# SD.net
KiCad netlist of a schematic drawn in Altium Designer
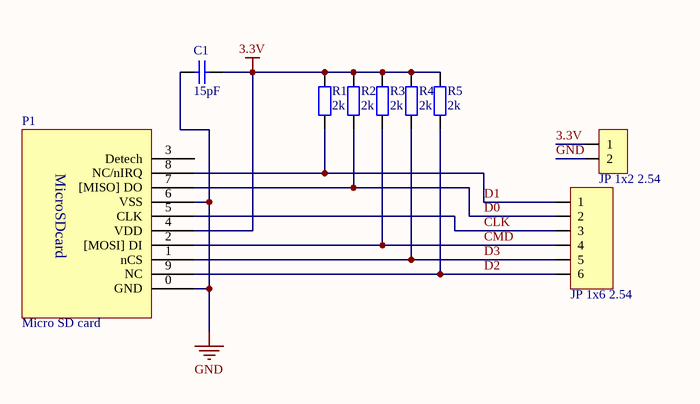
[diagram p0: SD.SchDoc]

(export (version "E")
  (design (tool "Eeschema 10.0.6"))
  (components
    (comp (ref "C1")
      (value "15pF")
      (footprint "tu 0805")
      (description "Dán")
      (libsource (lib "Capacitor") (part "Tu 0805 15pF 50V 10%"))
    )
    (comp (ref "JP1")
      (value "JP 1x6 2.54")
      (footprint "JP 1x6 DT")
      (description "Cắm")
      (libsource (lib "Jump") (part "JP 1x6 2.54 Duc Thang"))
    )
    (comp (ref "JP3")
      (value "JP 1x2 2.54")
      (footprint "JP 1x2 DT")
      (description "Cắm")
      (libsource (lib "Jump") (part "JP 1x2 2.54 Duc Thang"))
    )
    (comp (ref "P1")
      (value "Micro SD card")
      (footprint "MicroSD")
      (libsource (lib "Component") (part "Micro SD card"))
    )
    (comp (ref "R1")
      (value "2k")
      (footprint "tro smd 0805")
      (description "Dán")
      (libsource (lib "Resistor") (part "Tro 0805 1% 2k"))
    )
    (comp (ref "R2")
      (value "2k")
      (footprint "tro smd 0805")
      (description "Dán")
      (libsource (lib "Resistor") (part "Tro 0805 1% 2k"))
    )
    (comp (ref "R3")
      (value "2k")
      (footprint "tro smd 0805")
      (description "Dán")
      (libsource (lib "Resistor") (part "Tro 0805 1% 2k"))
    )
    (comp (ref "R4")
      (value "2k")
      (footprint "tro smd 0805")
      (description "Dán")
      (libsource (lib "Resistor") (part "Tro 0805 1% 2k"))
    )
    (comp (ref "R5")
      (value "2k")
      (footprint "tro smd 0805")
      (description "Dán")
      (libsource (lib "Resistor") (part "Tro 0805 1% 2k"))
    )
  )
  (nets
    (net (code "1") (name "/CLK") (class "Default")
      (node (ref "JP1") (pin "3") (pinfunction "3_3") (pintype "passive"))
      (node (ref "P1") (pin "5") (pinfunction "CLK_5") (pintype "passive"))
    )
    (net (code "2") (name "/CMD") (class "Default")
      (node (ref "JP1") (pin "4") (pinfunction "4_4") (pintype "passive"))
      (node (ref "P1") (pin "2") (pinfunction "[MOSI]_DI_2") (pintype "passive"))
      (node (ref "R3") (pin "1") (pinfunction "1_1") (pintype "passive"))
    )
    (net (code "3") (name "/D0") (class "Default")
      (node (ref "JP1") (pin "2") (pinfunction "2_2") (pintype "passive"))
      (node (ref "P1") (pin "7") (pinfunction "[MISO]_DO_7") (pintype "passive"))
      (node (ref "R2") (pin "1") (pinfunction "1_1") (pintype "passive"))
    )
    (net (code "4") (name "/D1") (class "Default")
      (node (ref "JP1") (pin "1") (pinfunction "1_1") (pintype "passive"))
      (node (ref "P1") (pin "8") (pinfunction "NC/nIRQ_8") (pintype "passive"))
      (node (ref "R1") (pin "1") (pinfunction "1_1") (pintype "passive"))
    )
    (net (code "5") (name "/D2") (class "Default")
      (node (ref "JP1") (pin "6") (pinfunction "6_6") (pintype "passive"))
      (node (ref "P1") (pin "9") (pinfunction "NC_9") (pintype "passive"))
      (node (ref "R5") (pin "1") (pinfunction "1_1") (pintype "passive"))
    )
    (net (code "6") (name "/D3") (class "Default")
      (node (ref "JP1") (pin "5") (pinfunction "5_5") (pintype "passive"))
      (node (ref "P1") (pin "1") (pinfunction "nCS_1") (pintype "passive"))
      (node (ref "R4") (pin "1") (pinfunction "1_1") (pintype "passive"))
    )
    (net (code "7") (name "3.3V") (class "Default")
      (node (ref "C1") (pin "1") (pinfunction "1_1") (pintype "passive"))
      (node (ref "JP3") (pin "1") (pinfunction "1_1") (pintype "passive"))
      (node (ref "P1") (pin "4") (pinfunction "VDD_4") (pintype "passive"))
      (node (ref "R1") (pin "2") (pinfunction "2_2") (pintype "passive"))
      (node (ref "R2") (pin "2") (pinfunction "2_2") (pintype "passive"))
      (node (ref "R3") (pin "2") (pinfunction "2_2") (pintype "passive"))
      (node (ref "R4") (pin "2") (pinfunction "2_2") (pintype "passive"))
      (node (ref "R5") (pin "2") (pinfunction "2_2") (pintype "passive"))
    )
    (net (code "8") (name "GND") (class "Default")
      (node (ref "C1") (pin "2") (pinfunction "2_2") (pintype "passive"))
      (node (ref "JP3") (pin "2") (pinfunction "2_2") (pintype "passive"))
      (node (ref "P1") (pin "0") (pinfunction "GND_0") (pintype "passive"))
      (node (ref "P1") (pin "6") (pinfunction "VSS_6") (pintype "passive"))
    )
    (net (code "9") (name "unconnected-(P1-Detech-Pad3)") (class "Default")
      (node (ref "P1") (pin "3") (pinfunction "Detech_3") (pintype "passive"))
    )
  )
)
